# Lighting.net
KiCad netlist of a schematic drawn in Altium Designer
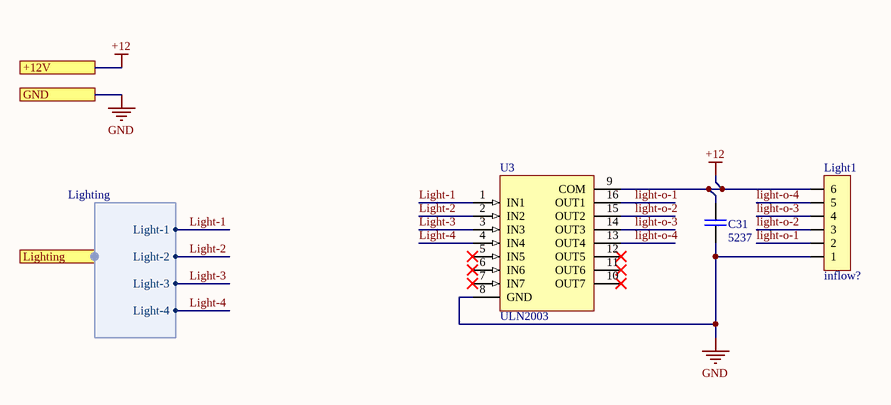
[diagram p0: Lighting.SchDoc]

(export (version "E")
  (design (tool "Eeschema 10.0.6"))
  (components
    (comp (ref "C31")
      (value "1u'F, 50'V")
      (footprint "CAP 1206/3216")
      (description "Bipolar ceramic capacitor SMD")
      (fields (field (name "INFLOW") "5237") (field (name "VALIDATION") "Valid"))
      (libsource (lib "aKaReZa") (part "Cap_Multi_1u_50_1206"))
    )
    (comp (ref "Light1")
      (value "6'Pin")
      (footprint "MOLEX KK 0022272061")
      (description "Signal Connector 6'Pin")
      (fields (field (name "INFLOW") "inflow?") (field (name "VALIDATION") "Valid"))
      (libsource (lib "aKaReZa") (part "Con_Signal_6"))
    )
    (comp (ref "U3")
      (value "ULN2003")
      (footprint "SO16_M")
      (description "Seven darlington array drivers")
      (fields (field (name "VALIDATION") "Valid"))
      (libsource (lib "vending-pad-002") (part "IC_Driver_ULN2003"))
    )
  )
  (nets
    (net (code "2") (name "+12") (class "Default")
      (node (ref "C31") (pin "2") (pinfunction "2_2") (pintype "passive"))
      (node (ref "Light1") (pin "6") (pinfunction "6_6") (pintype "passive"))
      (node (ref "U3") (pin "9") (pinfunction "COM_9") (pintype "passive"))
    )
    (net (code "3") (name "/Light-1") (class "Default")
      (node (ref "U3") (pin "1") (pinfunction "IN1_1") (pintype "input"))
    )
    (net (code "4") (name "/Light-2") (class "Default")
      (node (ref "U3") (pin "2") (pinfunction "IN2_2") (pintype "input"))
    )
    (net (code "5") (name "/Light-3") (class "Default")
      (node (ref "U3") (pin "3") (pinfunction "IN3_3") (pintype "input"))
    )
    (net (code "6") (name "/Light-4") (class "Default")
      (node (ref "U3") (pin "4") (pinfunction "IN4_4") (pintype "input"))
    )
    (net (code "7") (name "/light-o-1") (class "Default")
      (node (ref "Light1") (pin "2") (pinfunction "2_2") (pintype "passive"))
      (node (ref "U3") (pin "16") (pinfunction "OUT1_16") (pintype "open_collector"))
    )
    (net (code "8") (name "/light-o-2") (class "Default")
      (node (ref "Light1") (pin "3") (pinfunction "3_3") (pintype "passive"))
      (node (ref "U3") (pin "15") (pinfunction "OUT2_15") (pintype "open_collector"))
    )
    (net (code "9") (name "/light-o-3") (class "Default")
      (node (ref "Light1") (pin "4") (pinfunction "4_4") (pintype "passive"))
      (node (ref "U3") (pin "14") (pinfunction "OUT3_14") (pintype "open_collector"))
    )
    (net (code "10") (name "/light-o-4") (class "Default")
      (node (ref "Light1") (pin "5") (pinfunction "5_5") (pintype "passive"))
      (node (ref "U3") (pin "13") (pinfunction "OUT4_13") (pintype "open_collector"))
    )
    (net (code "12") (name "GND") (class "Default")
      (node (ref "C31") (pin "1") (pinfunction "1_1") (pintype "passive"))
      (node (ref "Light1") (pin "1") (pinfunction "1_1") (pintype "passive"))
      (node (ref "U3") (pin "8") (pinfunction "GND_8") (pintype "power_in"))
    )
    (net (code "13") (name "unconnected-(U3-IN5-Pad5)") (class "Default")
      (node (ref "U3") (pin "5") (pinfunction "IN5_5") (pintype "input+no_connect"))
    )
    (net (code "14") (name "unconnected-(U3-IN6-Pad6)") (class "Default")
      (node (ref "U3") (pin "6") (pinfunction "IN6_6") (pintype "input+no_connect"))
    )
    (net (code "15") (name "unconnected-(U3-IN7-Pad7)") (class "Default")
      (node (ref "U3") (pin "7") (pinfunction "IN7_7") (pintype "input+no_connect"))
    )
    (net (code "16") (name "unconnected-(U3-OUT5-Pad12)") (class "Default")
      (node (ref "U3") (pin "12") (pinfunction "OUT5_12") (pintype "open_collector+no_connect"))
    )
    (net (code "17") (name "unconnected-(U3-OUT6-Pad11)") (class "Default")
      (node (ref "U3") (pin "11") (pinfunction "OUT6_11") (pintype "open_collector+no_connect"))
    )
    (net (code "18") (name "unconnected-(U3-OUT7-Pad10)") (class "Default")
      (node (ref "U3") (pin "10") (pinfunction "OUT7_10") (pintype "open_collector+no_connect"))
    )
  )
)
